# LNA_1_7GHz_main_board.net
KiCad netlist of a schematic drawn in Altium Designer
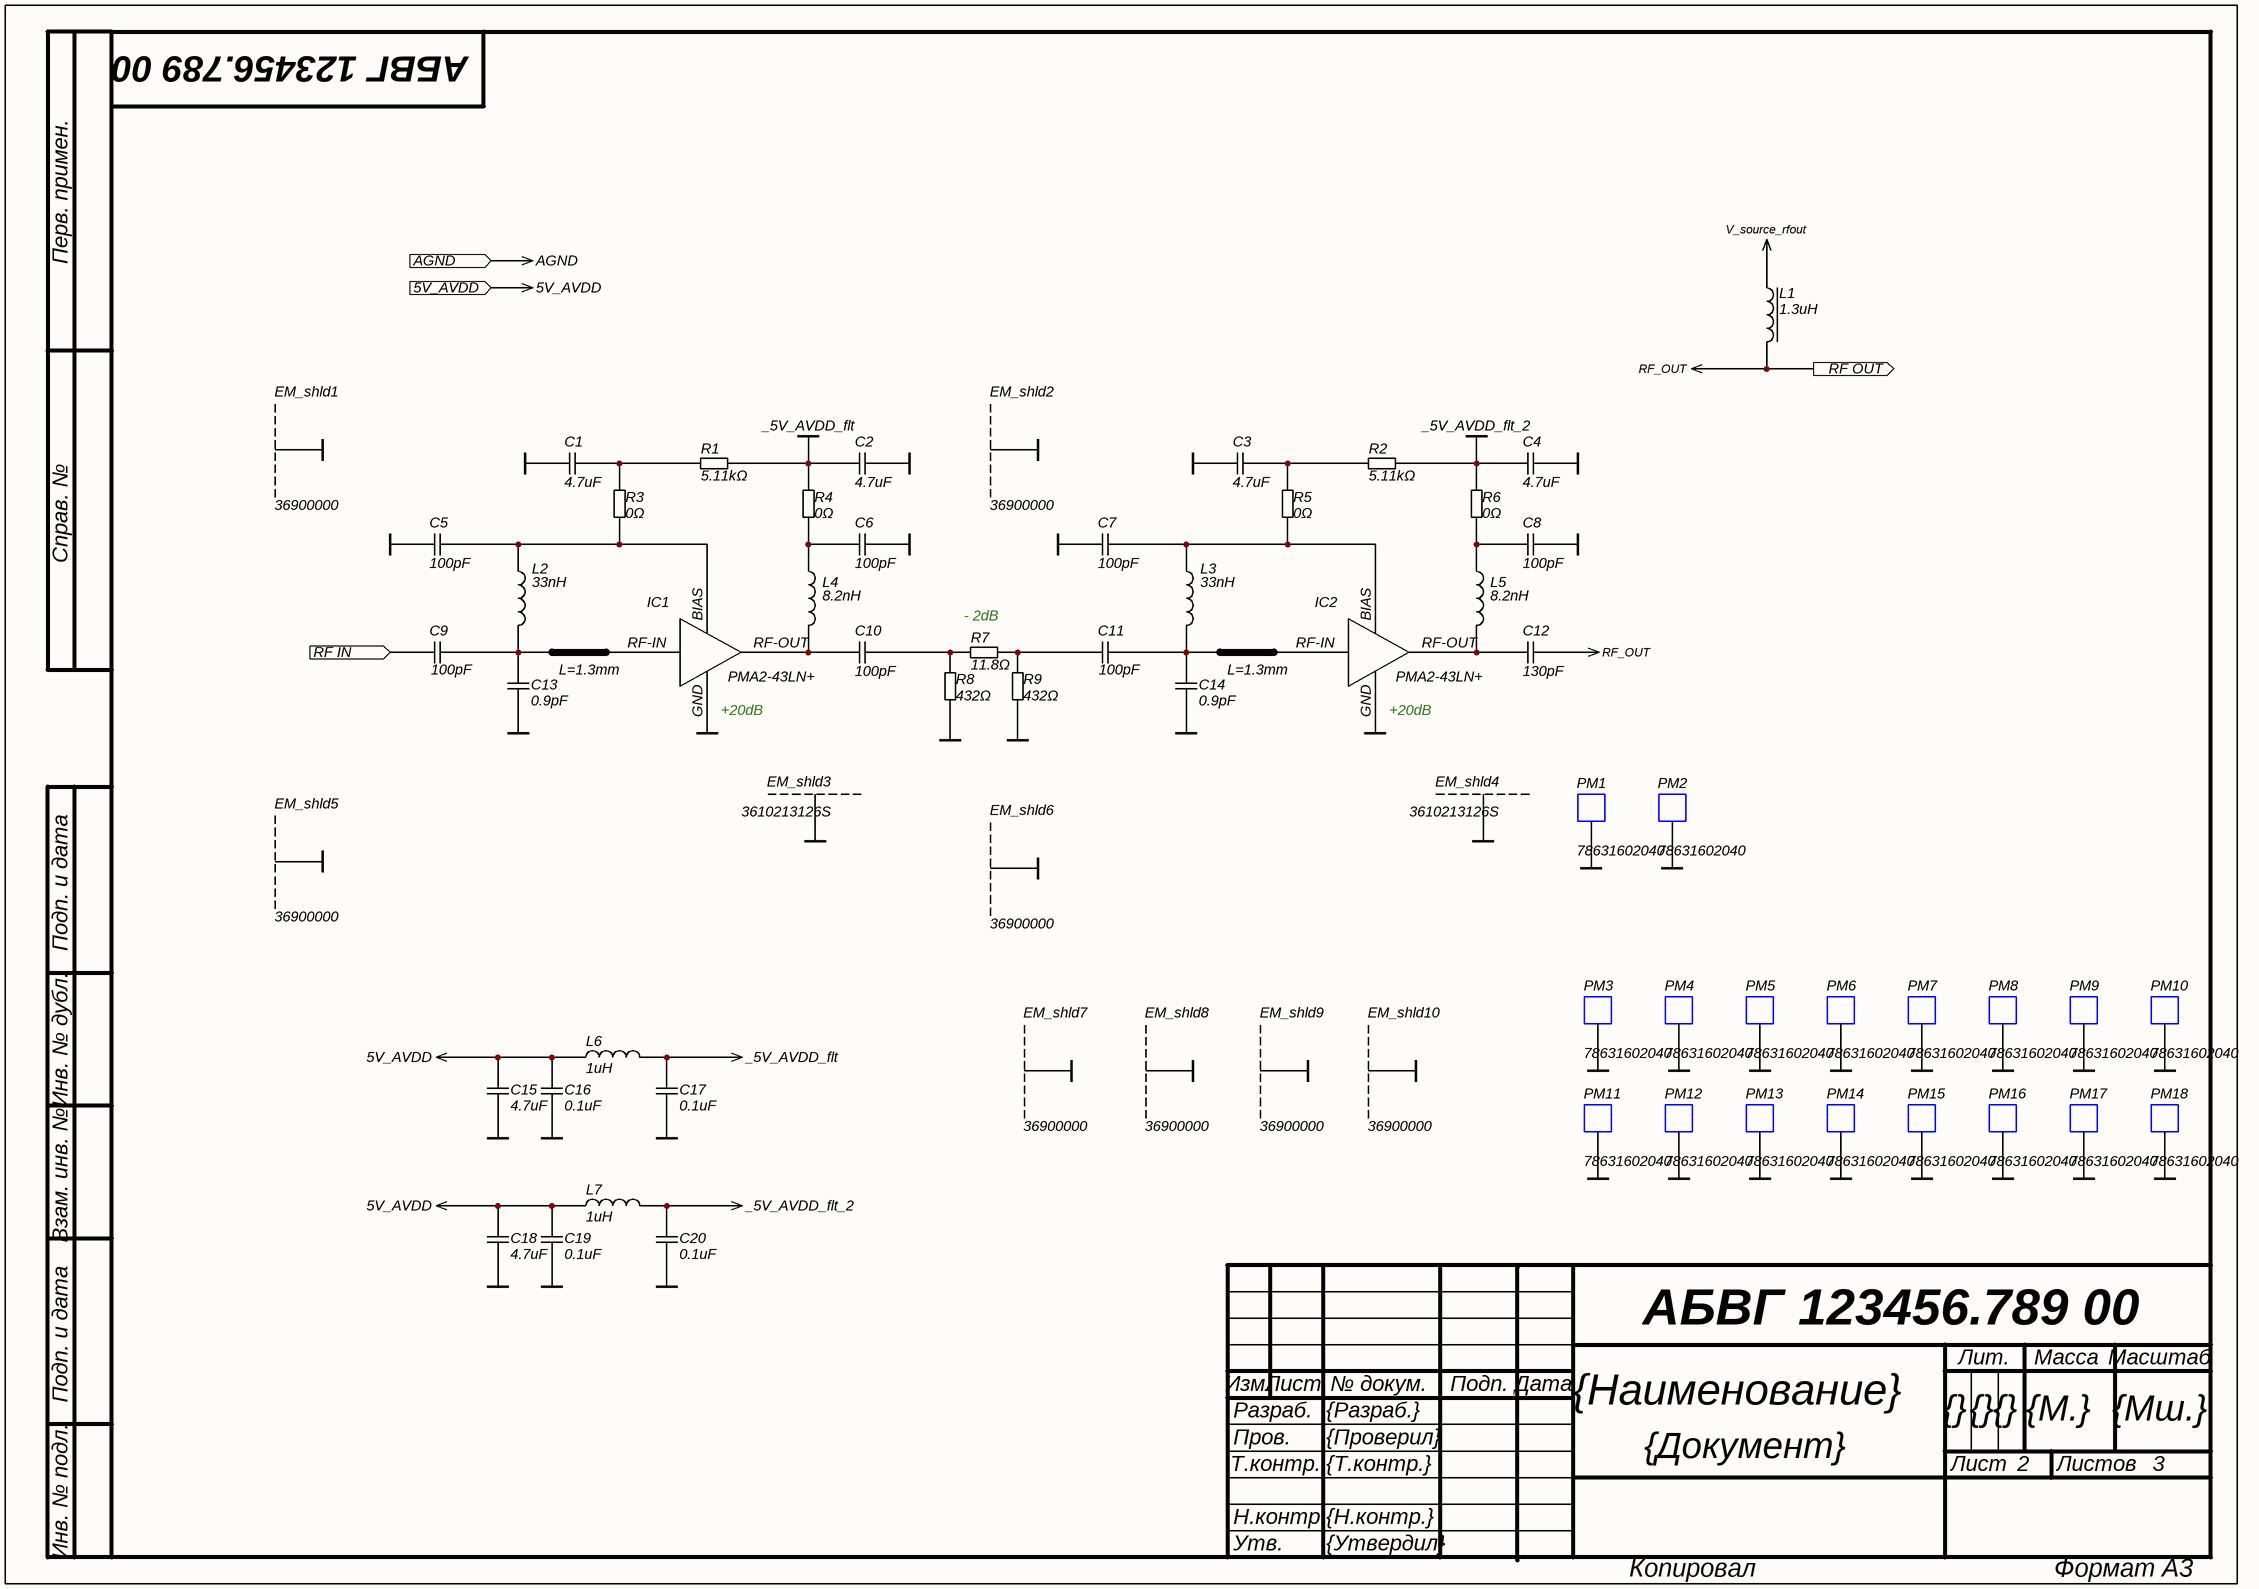
[diagram p0: LNA_1.7GHz_main_board.SchDoc]

(export (version "E")
  (design (tool "Eeschema 10.0.6"))
  (components
    (comp (ref "C1")
      (value "4.7uF")
      (footprint "LNA_1.7GHz:C0603")
      (description "Керамический конденсатор")
      (libsource (lib "LNA_1.7GHz") (part "CAP"))
    )
    (comp (ref "C2")
      (value "4.7uF")
      (footprint "LNA_1.7GHz:C0603")
      (description "Керамический конденсатор")
      (libsource (lib "LNA_1.7GHz") (part "CAP"))
    )
    (comp (ref "C3")
      (value "4.7uF")
      (footprint "LNA_1.7GHz:C0603")
      (description "Керамический конденсатор")
      (libsource (lib "LNA_1.7GHz") (part "CAP"))
    )
    (comp (ref "C4")
      (value "4.7uF")
      (footprint "LNA_1.7GHz:C0603")
      (description "Керамический конденсатор")
      (libsource (lib "LNA_1.7GHz") (part "CAP"))
    )
    (comp (ref "C5")
      (value "100pF")
      (footprint "LNA_1.7GHz:C0603")
      (description "Керамический конденсатор")
      (libsource (lib "LNA_1.7GHz") (part "CAP"))
    )
    (comp (ref "C6")
      (value "100pF")
      (footprint "LNA_1.7GHz:C0603")
      (description "Керамический конденсатор")
      (libsource (lib "LNA_1.7GHz") (part "CAP"))
    )
    (comp (ref "C7")
      (value "100pF")
      (footprint "LNA_1.7GHz:C0603")
      (description "Керамический конденсатор")
      (libsource (lib "LNA_1.7GHz") (part "CAP"))
    )
    (comp (ref "C8")
      (value "100pF")
      (footprint "LNA_1.7GHz:C0603")
      (description "Керамический конденсатор")
      (libsource (lib "LNA_1.7GHz") (part "CAP"))
    )
    (comp (ref "C9")
      (value "100pF")
      (footprint "LNA_1.7GHz:C0603")
      (description "Керамический конденсатор")
      (libsource (lib "LNA_1.7GHz") (part "CAP"))
    )
    (comp (ref "C10")
      (value "100pF")
      (footprint "LNA_1.7GHz:C0603")
      (description "Керамический конденсатор")
      (libsource (lib "LNA_1.7GHz") (part "CAP"))
    )
    (comp (ref "C11")
      (value "100pF")
      (footprint "LNA_1.7GHz:C0603")
      (description "Керамический конденсатор")
      (libsource (lib "LNA_1.7GHz") (part "CAP"))
    )
    (comp (ref "C12")
      (value "130pF")
      (footprint "LNA_1.7GHz:C0603")
      (description "Керамический конденсатор")
      (libsource (lib "LNA_1.7GHz") (part "CAP"))
    )
    (comp (ref "C13")
      (value "0.9pF")
      (footprint "LNA_1.7GHz:C0603")
      (description "Керамический конденсатор")
      (libsource (lib "LNA_1.7GHz") (part "CAP"))
    )
    (comp (ref "C14")
      (value "0.9pF")
      (footprint "LNA_1.7GHz:C0603")
      (description "Керамический конденсатор")
      (libsource (lib "LNA_1.7GHz") (part "CAP"))
    )
    (comp (ref "C15")
      (value "4.7uF")
      (footprint "LNA_1.7GHz:C0603")
      (description "Керамический конденсатор")
      (libsource (lib "LNA_1.7GHz") (part "CAP"))
    )
    (comp (ref "C16")
      (value "0.1uF")
      (footprint "LNA_1.7GHz:C0603")
      (description "Керамический конденсатор")
      (libsource (lib "LNA_1.7GHz") (part "CAP"))
    )
    (comp (ref "C17")
      (value "0.1uF")
      (footprint "LNA_1.7GHz:C0603")
      (description "Керамический конденсатор")
      (libsource (lib "LNA_1.7GHz") (part "CAP"))
    )
    (comp (ref "C18")
      (value "4.7uF")
      (footprint "LNA_1.7GHz:C0603")
      (description "Керамический конденсатор")
      (libsource (lib "LNA_1.7GHz") (part "CAP"))
    )
    (comp (ref "C19")
      (value "0.1uF")
      (footprint "LNA_1.7GHz:C0603")
      (description "Керамический конденсатор")
      (libsource (lib "LNA_1.7GHz") (part "CAP"))
    )
    (comp (ref "C20")
      (value "0.1uF")
      (footprint "LNA_1.7GHz:C0603")
      (description "Керамический конденсатор")
      (libsource (lib "LNA_1.7GHz") (part "CAP"))
    )
    (comp (ref "EM_shld1")
      (value "36900000")
      (footprint "WE-SHC:36900000")
      (description "RF Shield Frame X 0.522\" (13.26mm) Surface Mount")
      (libsource (lib "LNA_1.7GHz") (part "RF Shield"))
    )
    (comp (ref "EM_shld2")
      (value "36900000")
      (footprint "WE-SHC:36900000")
      (description "RF Shield Frame X 0.522\" (13.26mm) Surface Mount")
      (libsource (lib "LNA_1.7GHz") (part "RF Shield"))
    )
    (comp (ref "EM_shld3")
      (value "3610213126S")
      (footprint "WE-SHC:3610213126S")
      (description "RF Shield Frame X 0.522\" (13.26mm) Surface Mount")
      (libsource (lib "LNA_1.7GHz") (part "RF Shield"))
    )
    (comp (ref "EM_shld4")
      (value "3610213126S")
      (footprint "WE-SHC:3610213126S")
      (description "RF Shield Frame X 0.522\" (13.26mm) Surface Mount")
      (libsource (lib "LNA_1.7GHz") (part "RF Shield"))
    )
    (comp (ref "EM_shld5")
      (value "36900000")
      (footprint "WE-SHC:36900000")
      (description "RF Shield Frame X 0.522\" (13.26mm) Surface Mount")
      (libsource (lib "LNA_1.7GHz") (part "RF Shield"))
    )
    (comp (ref "EM_shld6")
      (value "36900000")
      (footprint "WE-SHC:36900000")
      (description "RF Shield Frame X 0.522\" (13.26mm) Surface Mount")
      (libsource (lib "LNA_1.7GHz") (part "RF Shield"))
    )
    (comp (ref "EM_shld7")
      (value "36900000")
      (footprint "WE-SHC:36900000")
      (description "RF Shield Frame X 0.522\" (13.26mm) Surface Mount")
      (libsource (lib "LNA_1.7GHz") (part "RF Shield"))
    )
    (comp (ref "EM_shld8")
      (value "36900000")
      (footprint "WE-SHC:36900000")
      (description "RF Shield Frame X 0.522\" (13.26mm) Surface Mount")
      (libsource (lib "LNA_1.7GHz") (part "RF Shield"))
    )
    (comp (ref "EM_shld9")
      (value "36900000")
      (footprint "WE-SHC:36900000")
      (description "RF Shield Frame X 0.522\" (13.26mm) Surface Mount")
      (libsource (lib "LNA_1.7GHz") (part "RF Shield"))
    )
    (comp (ref "EM_shld10")
      (value "36900000")
      (footprint "WE-SHC:36900000")
      (description "RF Shield Frame X 0.522\" (13.26mm) Surface Mount")
      (libsource (lib "LNA_1.7GHz") (part "RF Shield"))
    )
    (comp (ref "IC1")
      (value "PMA2-43LN+")
      (footprint "LNA_1.7GHz:MC1631-1_MNC-L")
      (description "Малошумяший усилитель")
      (libsource (lib "LNA_1.7GHz") (part "PMA2-43LN+"))
    )
    (comp (ref "IC2")
      (value "PMA2-43LN+")
      (footprint "LNA_1.7GHz:MC1631-1_MNC-L")
      (description "Малошумяший усилитель")
      (libsource (lib "LNA_1.7GHz") (part "PMA2-43LN+"))
    )
    (comp (ref "L1")
      (value "1.3uH")
      (footprint "LNA_1.7GHz:4310LC")
      (description "Индуктивность")
      (libsource (lib "LNA_1.7GHz") (part "4310LC"))
    )
    (comp (ref "L2")
      (value "33nH")
      (footprint "LNA_1.7GHz:L0603_HP")
      (description "Индуктивность")
      (libsource (lib "LNA_1.7GHz") (part "Inducror RF"))
    )
    (comp (ref "L3")
      (value "33nH")
      (footprint "LNA_1.7GHz:L0603_HP")
      (description "Индуктивность")
      (libsource (lib "LNA_1.7GHz") (part "Inducror RF"))
    )
    (comp (ref "L4")
      (value "8.2nH")
      (footprint "LNA_1.7GHz:L0603_HP")
      (description "Индуктивность")
      (libsource (lib "LNA_1.7GHz") (part "Inducror RF"))
    )
    (comp (ref "L5")
      (value "8.2nH")
      (footprint "LNA_1.7GHz:L0603_HP")
      (description "Индуктивность")
      (libsource (lib "LNA_1.7GHz") (part "Inducror RF"))
    )
    (comp (ref "L6")
      (value "1uH")
      (footprint "Kintex_SDR:L1206_Murata")
      (description "Индуктивность")
      (libsource (lib "LNA_1.7GHz") (part "Inducror LF"))
    )
    (comp (ref "L7")
      (value "1uH")
      (footprint "Kintex_SDR:L1206_Murata")
      (description "Индуктивность")
      (libsource (lib "LNA_1.7GHz") (part "Inducror LF"))
    )
    (comp (ref "PM1")
      (value "78631602040")
      (footprint "LNA_1.7GHz:78631602040")
      (description "WE-SCFA Soldered Contact Finger Automotive, L6W2H4mm, Working Height 5~5.7mm")
      (libsource (lib "LNA_1.7GHz") (part "78631602040"))
    )
    (comp (ref "PM2")
      (value "78631602040")
      (footprint "LNA_1.7GHz:78631602040")
      (description "WE-SCFA Soldered Contact Finger Automotive, L6W2H4mm, Working Height 5~5.7mm")
      (libsource (lib "LNA_1.7GHz") (part "78631602040"))
    )
    (comp (ref "PM3")
      (value "78631602040")
      (footprint "LNA_1.7GHz:78631602040")
      (description "WE-SCFA Soldered Contact Finger Automotive, L6W2H4mm, Working Height 5~5.7mm")
      (libsource (lib "LNA_1.7GHz") (part "78631602040"))
    )
    (comp (ref "PM4")
      (value "78631602040")
      (footprint "LNA_1.7GHz:78631602040")
      (description "WE-SCFA Soldered Contact Finger Automotive, L6W2H4mm, Working Height 5~5.7mm")
      (libsource (lib "LNA_1.7GHz") (part "78631602040"))
    )
    (comp (ref "PM5")
      (value "78631602040")
      (footprint "LNA_1.7GHz:78631602040")
      (description "WE-SCFA Soldered Contact Finger Automotive, L6W2H4mm, Working Height 5~5.7mm")
      (libsource (lib "LNA_1.7GHz") (part "78631602040"))
    )
    (comp (ref "PM6")
      (value "78631602040")
      (footprint "LNA_1.7GHz:78631602040")
      (description "WE-SCFA Soldered Contact Finger Automotive, L6W2H4mm, Working Height 5~5.7mm")
      (libsource (lib "LNA_1.7GHz") (part "78631602040"))
    )
    (comp (ref "PM7")
      (value "78631602040")
      (footprint "LNA_1.7GHz:78631602040")
      (description "WE-SCFA Soldered Contact Finger Automotive, L6W2H4mm, Working Height 5~5.7mm")
      (libsource (lib "LNA_1.7GHz") (part "78631602040"))
    )
    (comp (ref "PM8")
      (value "78631602040")
      (footprint "LNA_1.7GHz:78631602040")
      (description "WE-SCFA Soldered Contact Finger Automotive, L6W2H4mm, Working Height 5~5.7mm")
      (libsource (lib "LNA_1.7GHz") (part "78631602040"))
    )
    (comp (ref "PM9")
      (value "78631602040")
      (footprint "LNA_1.7GHz:78631602040")
      (description "WE-SCFA Soldered Contact Finger Automotive, L6W2H4mm, Working Height 5~5.7mm")
      (libsource (lib "LNA_1.7GHz") (part "78631602040"))
    )
    (comp (ref "PM10")
      (value "78631602040")
      (footprint "LNA_1.7GHz:78631602040")
      (description "WE-SCFA Soldered Contact Finger Automotive, L6W2H4mm, Working Height 5~5.7mm")
      (libsource (lib "LNA_1.7GHz") (part "78631602040"))
    )
    (comp (ref "PM11")
      (value "78631602040")
      (footprint "LNA_1.7GHz:78631602040")
      (description "WE-SCFA Soldered Contact Finger Automotive, L6W2H4mm, Working Height 5~5.7mm")
      (libsource (lib "LNA_1.7GHz") (part "78631602040"))
    )
    (comp (ref "PM12")
      (value "78631602040")
      (footprint "LNA_1.7GHz:78631602040")
      (description "WE-SCFA Soldered Contact Finger Automotive, L6W2H4mm, Working Height 5~5.7mm")
      (libsource (lib "LNA_1.7GHz") (part "78631602040"))
    )
    (comp (ref "PM13")
      (value "78631602040")
      (footprint "LNA_1.7GHz:78631602040")
      (description "WE-SCFA Soldered Contact Finger Automotive, L6W2H4mm, Working Height 5~5.7mm")
      (libsource (lib "LNA_1.7GHz") (part "78631602040"))
    )
    (comp (ref "PM14")
      (value "78631602040")
      (footprint "LNA_1.7GHz:78631602040")
      (description "WE-SCFA Soldered Contact Finger Automotive, L6W2H4mm, Working Height 5~5.7mm")
      (libsource (lib "LNA_1.7GHz") (part "78631602040"))
    )
    (comp (ref "PM15")
      (value "78631602040")
      (footprint "LNA_1.7GHz:78631602040")
      (description "WE-SCFA Soldered Contact Finger Automotive, L6W2H4mm, Working Height 5~5.7mm")
      (libsource (lib "LNA_1.7GHz") (part "78631602040"))
    )
    (comp (ref "PM16")
      (value "78631602040")
      (footprint "LNA_1.7GHz:78631602040")
      (description "WE-SCFA Soldered Contact Finger Automotive, L6W2H4mm, Working Height 5~5.7mm")
      (libsource (lib "LNA_1.7GHz") (part "78631602040"))
    )
    (comp (ref "PM17")
      (value "78631602040")
      (footprint "LNA_1.7GHz:78631602040")
      (description "WE-SCFA Soldered Contact Finger Automotive, L6W2H4mm, Working Height 5~5.7mm")
      (libsource (lib "LNA_1.7GHz") (part "78631602040"))
    )
    (comp (ref "PM18")
      (value "78631602040")
      (footprint "LNA_1.7GHz:78631602040")
      (description "WE-SCFA Soldered Contact Finger Automotive, L6W2H4mm, Working Height 5~5.7mm")
      (libsource (lib "LNA_1.7GHz") (part "78631602040"))
    )
    (comp (ref "R1")
      (value "5.11kΩ")
      (footprint "LNA_1.7GHz:R0603")
      (description "SMD резистор")
      (libsource (lib "") (part "RES_2"))
    )
    (comp (ref "R2")
      (value "5.11kΩ")
      (footprint "LNA_1.7GHz:R0603")
      (description "SMD резистор")
      (libsource (lib "") (part "RES_2"))
    )
    (comp (ref "R3")
      (value "0Ω")
      (footprint "LNA_1.7GHz:R0603")
      (description "SMD резистор")
      (libsource (lib "LNA_1.7GHz") (part "RES"))
    )
    (comp (ref "R4")
      (value "0Ω")
      (footprint "LNA_1.7GHz:R0603")
      (description "SMD резистор")
      (libsource (lib "LNA_1.7GHz") (part "RES"))
    )
    (comp (ref "R5")
      (value "0Ω")
      (footprint "LNA_1.7GHz:R0603")
      (description "SMD резистор")
      (libsource (lib "LNA_1.7GHz") (part "RES"))
    )
    (comp (ref "R6")
      (value "0Ω")
      (footprint "LNA_1.7GHz:R0603")
      (description "SMD резистор")
      (libsource (lib "LNA_1.7GHz") (part "RES"))
    )
    (comp (ref "R7")
      (value "11.8Ω")
      (footprint "LNA_1.7GHz:R0603")
      (description "SMD резистор")
      (libsource (lib "") (part "RES_2"))
    )
    (comp (ref "R8")
      (value "432Ω")
      (footprint "LNA_1.7GHz:R0603")
      (description "SMD резистор")
      (libsource (lib "") (part "RES_1"))
    )
    (comp (ref "R9")
      (value "432Ω")
      (footprint "LNA_1.7GHz:R0603")
      (description "SMD резистор")
      (libsource (lib "") (part "RES_1"))
    )
  )
  (nets
    (net (code "1") (name "/RF IN") (class "Default")
      (node (ref "C9") (pin "1") (pinfunction "1_1") (pintype "passive"))
    )
    (net (code "2") (name "5V_AVDD") (class "Default")
      (node (ref "C15") (pin "2") (pinfunction "2_2") (pintype "passive"))
      (node (ref "C16") (pin "2") (pinfunction "2_2") (pintype "passive"))
      (node (ref "C18") (pin "2") (pinfunction "2_2") (pintype "passive"))
      (node (ref "C19") (pin "2") (pinfunction "2_2") (pintype "passive"))
      (node (ref "L6") (pin "2") (pinfunction "2_2") (pintype "passive"))
      (node (ref "L7") (pin "2") (pinfunction "2_2") (pintype "passive"))
    )
    (net (code "3") (name "AGND") (class "Default")
      (node (ref "C1") (pin "1") (pinfunction "1_1") (pintype "passive"))
      (node (ref "C13") (pin "1") (pinfunction "1_1") (pintype "passive"))
      (node (ref "C14") (pin "1") (pinfunction "1_1") (pintype "passive"))
      (node (ref "C15") (pin "1") (pinfunction "1_1") (pintype "passive"))
      (node (ref "C16") (pin "1") (pinfunction "1_1") (pintype "passive"))
      (node (ref "C17") (pin "1") (pinfunction "1_1") (pintype "passive"))
      (node (ref "C18") (pin "1") (pinfunction "1_1") (pintype "passive"))
      (node (ref "C19") (pin "1") (pinfunction "1_1") (pintype "passive"))
      (node (ref "C2") (pin "2") (pinfunction "2_2") (pintype "passive"))
      (node (ref "C20") (pin "1") (pinfunction "1_1") (pintype "passive"))
      (node (ref "C3") (pin "1") (pinfunction "1_1") (pintype "passive"))
      (node (ref "C4") (pin "2") (pinfunction "2_2") (pintype "passive"))
      (node (ref "C5") (pin "1") (pinfunction "1_1") (pintype "passive"))
      (node (ref "C6") (pin "2") (pinfunction "2_2") (pintype "passive"))
      (node (ref "C7") (pin "1") (pinfunction "1_1") (pintype "passive"))
      (node (ref "C8") (pin "2") (pinfunction "2_2") (pintype "passive"))
      (node (ref "EM_shld1") (pin "1") (pinfunction "1_1") (pintype "passive"))
      (node (ref "EM_shld10") (pin "1") (pinfunction "1_1") (pintype "passive"))
      (node (ref "EM_shld2") (pin "1") (pinfunction "1_1") (pintype "passive"))
      (node (ref "EM_shld3") (pin "1") (pinfunction "1_1") (pintype "passive"))
      (node (ref "EM_shld4") (pin "1") (pinfunction "1_1") (pintype "passive"))
      (node (ref "EM_shld5") (pin "1") (pinfunction "1_1") (pintype "passive"))
      (node (ref "EM_shld6") (pin "1") (pinfunction "1_1") (pintype "passive"))
      (node (ref "EM_shld7") (pin "1") (pinfunction "1_1") (pintype "passive"))
      (node (ref "EM_shld8") (pin "1") (pinfunction "1_1") (pintype "passive"))
      (node (ref "EM_shld9") (pin "1") (pinfunction "1_1") (pintype "passive"))
      (node (ref "IC1") (pin "GND") (pinfunction "GND_GND") (pintype "passive"))
      (node (ref "IC2") (pin "GND") (pinfunction "GND_GND") (pintype "passive"))
      (node (ref "PM1") (pin "1") (pinfunction "1_1") (pintype "passive"))
      (node (ref "PM10") (pin "1") (pinfunction "1_1") (pintype "passive"))
      (node (ref "PM11") (pin "1") (pinfunction "1_1") (pintype "passive"))
      (node (ref "PM12") (pin "1") (pinfunction "1_1") (pintype "passive"))
      (node (ref "PM13") (pin "1") (pinfunction "1_1") (pintype "passive"))
      (node (ref "PM14") (pin "1") (pinfunction "1_1") (pintype "passive"))
      (node (ref "PM15") (pin "1") (pinfunction "1_1") (pintype "passive"))
      (node (ref "PM16") (pin "1") (pinfunction "1_1") (pintype "passive"))
      (node (ref "PM17") (pin "1") (pinfunction "1_1") (pintype "passive"))
      (node (ref "PM18") (pin "1") (pinfunction "1_1") (pintype "passive"))
      (node (ref "PM2") (pin "1") (pinfunction "1_1") (pintype "passive"))
      (node (ref "PM3") (pin "1") (pinfunction "1_1") (pintype "passive"))
      (node (ref "PM4") (pin "1") (pinfunction "1_1") (pintype "passive"))
      (node (ref "PM5") (pin "1") (pinfunction "1_1") (pintype "passive"))
      (node (ref "PM6") (pin "1") (pinfunction "1_1") (pintype "passive"))
      (node (ref "PM7") (pin "1") (pinfunction "1_1") (pintype "passive"))
      (node (ref "PM8") (pin "1") (pinfunction "1_1") (pintype "passive"))
      (node (ref "PM9") (pin "1") (pinfunction "1_1") (pintype "passive"))
      (node (ref "R8") (pin "2") (pinfunction "2_2") (pintype "passive"))
      (node (ref "R9") (pin "2") (pinfunction "2_2") (pintype "passive"))
    )
    (net (code "4") (name "Net-(C1-Pad2)") (class "Default")
      (node (ref "C1") (pin "2") (pinfunction "2_2") (pintype "passive"))
      (node (ref "R1") (pin "2") (pinfunction "2_2") (pintype "passive"))
      (node (ref "R3") (pin "2") (pinfunction "2_2") (pintype "passive"))
    )
    (net (code "5") (name "Net-(C3-Pad2)") (class "Default")
      (node (ref "C3") (pin "2") (pinfunction "2_2") (pintype "passive"))
      (node (ref "R2") (pin "2") (pinfunction "2_2") (pintype "passive"))
      (node (ref "R5") (pin "2") (pinfunction "2_2") (pintype "passive"))
    )
    (net (code "6") (name "Net-(C5-Pad2)") (class "Default")
      (node (ref "C5") (pin "2") (pinfunction "2_2") (pintype "passive"))
      (node (ref "IC1") (pin "BIAS") (pinfunction "BIAS_BIAS") (pintype "passive"))
      (node (ref "L2") (pin "1") (pinfunction "1_1") (pintype "passive"))
      (node (ref "R3") (pin "1") (pinfunction "1_1") (pintype "passive"))
    )
    (net (code "7") (name "Net-(C6-Pad1)") (class "Default")
      (node (ref "C6") (pin "1") (pinfunction "1_1") (pintype "passive"))
      (node (ref "L4") (pin "1") (pinfunction "1_1") (pintype "passive"))
      (node (ref "R4") (pin "1") (pinfunction "1_1") (pintype "passive"))
    )
    (net (code "8") (name "Net-(C7-Pad2)") (class "Default")
      (node (ref "C7") (pin "2") (pinfunction "2_2") (pintype "passive"))
      (node (ref "IC2") (pin "BIAS") (pinfunction "BIAS_BIAS") (pintype "passive"))
      (node (ref "L3") (pin "1") (pinfunction "1_1") (pintype "passive"))
      (node (ref "R5") (pin "1") (pinfunction "1_1") (pintype "passive"))
    )
    (net (code "9") (name "Net-(C8-Pad1)") (class "Default")
      (node (ref "C8") (pin "1") (pinfunction "1_1") (pintype "passive"))
      (node (ref "L5") (pin "1") (pinfunction "1_1") (pintype "passive"))
      (node (ref "R6") (pin "1") (pinfunction "1_1") (pintype "passive"))
    )
    (net (code "10") (name "Net-(C10-Pad1)") (class "Default")
      (node (ref "C10") (pin "1") (pinfunction "1_1") (pintype "passive"))
      (node (ref "IC1") (pin "RF-OUT") (pinfunction "RF-OUT_RF-OUT") (pintype "passive"))
      (node (ref "L4") (pin "2") (pinfunction "2_2") (pintype "passive"))
    )
    (net (code "11") (name "Net-(C10-Pad2)") (class "Default")
      (node (ref "C10") (pin "2") (pinfunction "2_2") (pintype "passive"))
      (node (ref "R7") (pin "2") (pinfunction "2_2") (pintype "passive"))
      (node (ref "R8") (pin "1") (pinfunction "1_1") (pintype "passive"))
    )
    (net (code "12") (name "Net-(C11-Pad1)") (class "Default")
      (node (ref "C11") (pin "1") (pinfunction "1_1") (pintype "passive"))
      (node (ref "R7") (pin "1") (pinfunction "1_1") (pintype "passive"))
      (node (ref "R9") (pin "1") (pinfunction "1_1") (pintype "passive"))
    )
    (net (code "13") (name "Net-(C11-Pad2)") (class "Default")
      (node (ref "C11") (pin "2") (pinfunction "2_2") (pintype "passive"))
      (node (ref "C14") (pin "2") (pinfunction "2_2") (pintype "passive"))
      (node (ref "IC2") (pin "RF-IN") (pinfunction "RF-IN_RF-IN") (pintype "passive"))
      (node (ref "L3") (pin "2") (pinfunction "2_2") (pintype "passive"))
    )
    (net (code "14") (name "Net-(C12-Pad2)") (class "Default")
      (node (ref "C12") (pin "2") (pinfunction "2_2") (pintype "passive"))
      (node (ref "IC2") (pin "RF-OUT") (pinfunction "RF-OUT_RF-OUT") (pintype "passive"))
      (node (ref "L5") (pin "2") (pinfunction "2_2") (pintype "passive"))
    )
    (net (code "15") (name "Net-(C13-Pad2)") (class "Default")
      (node (ref "C13") (pin "2") (pinfunction "2_2") (pintype "passive"))
      (node (ref "C9") (pin "2") (pinfunction "2_2") (pintype "passive"))
      (node (ref "IC1") (pin "RF-IN") (pinfunction "RF-IN_RF-IN") (pintype "passive"))
      (node (ref "L2") (pin "2") (pinfunction "2_2") (pintype "passive"))
    )
    (net (code "16") (name "RF_OUT") (class "Default")
      (node (ref "C12") (pin "1") (pinfunction "1_1") (pintype "passive"))
      (node (ref "L1") (pin "1") (pinfunction "1_1") (pintype "passive"))
    )
    (net (code "17") (name "V_source_rfout") (class "Default")
      (node (ref "L1") (pin "2") (pinfunction "2_2") (pintype "passive"))
    )
    (net (code "18") (name "_5V_AVDD_flt") (class "Default")
      (node (ref "C17") (pin "2") (pinfunction "2_2") (pintype "passive"))
      (node (ref "C2") (pin "1") (pinfunction "1_1") (pintype "passive"))
      (node (ref "L6") (pin "1") (pinfunction "1_1") (pintype "passive"))
      (node (ref "R1") (pin "1") (pinfunction "1_1") (pintype "passive"))
      (node (ref "R4") (pin "2") (pinfunction "2_2") (pintype "passive"))
    )
    (net (code "19") (name "_5V_AVDD_flt_2") (class "Default")
      (node (ref "C20") (pin "2") (pinfunction "2_2") (pintype "passive"))
      (node (ref "C4") (pin "1") (pinfunction "1_1") (pintype "passive"))
      (node (ref "L7") (pin "1") (pinfunction "1_1") (pintype "passive"))
      (node (ref "R2") (pin "1") (pinfunction "1_1") (pintype "passive"))
      (node (ref "R6") (pin "2") (pinfunction "2_2") (pintype "passive"))
    )
  )
)
